# 1-Schematic_1d_Ping_Pong.net
KiCad netlist of a schematic drawn in EasyEDA
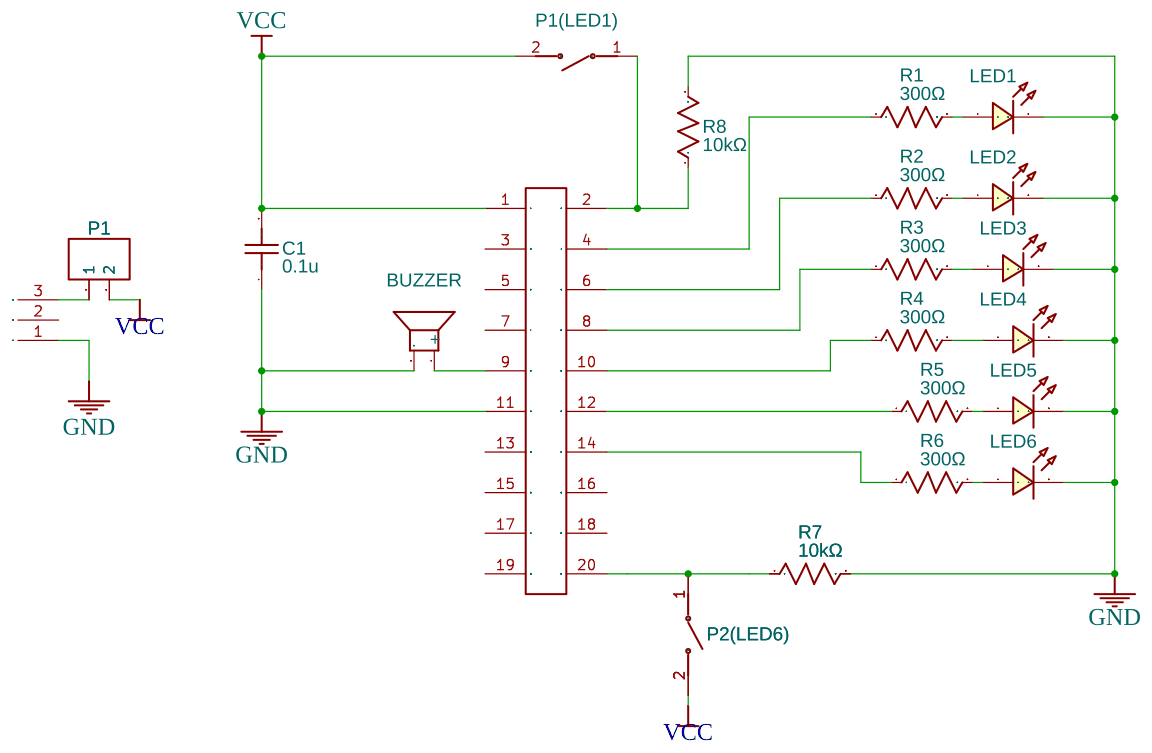
[diagram p0: schematic sheet]

(export (version "E")
  (design (tool "Eeschema 10.0.6"))
  (components
    (comp (ref "BUZZER")
      (value "BUZZER-12X9")
      (fields (field (name "Manufacturer Part") "buzzer-12X9"))
      (libsource (lib "") (part "BUZZER-12X9"))
    )
    (comp (ref "C1") (value "0.1u") (libsource (lib "") (part "C_0603_US")))
    (comp (ref "LED1")
      (value "LED-0603_R")
      (fields
        (field (name "Manufacturer Part") "19-217/R6C-AL1M2VY/3T")
        (field (name "Manufacturer") "EVERLIGHT(台湾亿光)")
      )
      (libsource (lib "") (part "LED-0603_R"))
    )
    (comp (ref "LED2")
      (value "LED-0603_R")
      (fields
        (field (name "Manufacturer Part") "19-217/R6C-AL1M2VY/3T")
        (field (name "Manufacturer") "EVERLIGHT(台湾亿光)")
      )
      (libsource (lib "") (part "LED-0603_R"))
    )
    (comp (ref "LED3")
      (value "LED-0603_R")
      (fields
        (field (name "Manufacturer Part") "19-217/R6C-AL1M2VY/3T")
        (field (name "Manufacturer") "EVERLIGHT(台湾亿光)")
      )
      (libsource (lib "") (part "LED-0603_R"))
    )
    (comp (ref "LED4")
      (value "LED-0603_R")
      (fields
        (field (name "Manufacturer Part") "19-217/R6C-AL1M2VY/3T")
        (field (name "Manufacturer") "EVERLIGHT(台湾亿光)")
      )
      (libsource (lib "") (part "LED-0603_R"))
    )
    (comp (ref "LED5")
      (value "LED-0603_R")
      (fields
        (field (name "Manufacturer Part") "19-217/R6C-AL1M2VY/3T")
        (field (name "Manufacturer") "EVERLIGHT(台湾亿光)")
      )
      (libsource (lib "") (part "LED-0603_R"))
    )
    (comp (ref "LED6")
      (value "LED-0603_R")
      (fields
        (field (name "Manufacturer Part") "19-217/R6C-AL1M2VY/3T")
        (field (name "Manufacturer") "EVERLIGHT(台湾亿光)")
      )
      (libsource (lib "") (part "LED-0603_R"))
    )
    (comp (ref "P1") (value "CONN-TH_2P-P5.00") (libsource (lib "") (part "CONN-TH_2P-P5.00")))
    (comp (ref "P1(LED1)") (value "BUTTON") (libsource (lib "") (part "BUTTON_1")))
    (comp (ref "P2(LED6)") (value "BUTTON") (libsource (lib "") (part "BUTTON")))
    (comp (ref "R1") (value "300Ω") (libsource (lib "") (part "R_0603_US")))
    (comp (ref "R2") (value "300Ω") (libsource (lib "") (part "R_0603_US")))
    (comp (ref "R3") (value "300Ω") (libsource (lib "") (part "R_0603_US")))
    (comp (ref "R4") (value "300Ω") (libsource (lib "") (part "R_0603_US")))
    (comp (ref "R5") (value "300Ω") (libsource (lib "") (part "R_0603_US")))
    (comp (ref "R6") (value "300Ω") (libsource (lib "") (part "R_0603_US")))
    (comp (ref "R7") (value "10kΩ") (libsource (lib "") (part "R_0603_US")))
    (comp (ref "R8") (value "10kΩ") (libsource (lib "") (part "R_0603_US_1")))
    (comp (ref "U1") (value "Tumbler_Large") (libsource (lib "") (part "Tumbler_Large")))
    (comp (ref "X1") (value "PIN_HEADER_2x10") (libsource (lib "") (part "PIN_HEADER_2x10")))
  )
  (nets
    (net (code "1") (name "GND") (class "Default")
      (node (ref "BUZZER") (pin "2") (pinfunction "2_2") (pintype "unspecified"))
      (node (ref "C1") (pin "1") (pinfunction "1_1") (pintype "unspecified"))
      (node (ref "LED1") (pin "2") (pinfunction "2_2") (pintype "unspecified"))
      (node (ref "LED2") (pin "2") (pinfunction "2_2") (pintype "unspecified"))
      (node (ref "LED3") (pin "2") (pinfunction "2_2") (pintype "unspecified"))
      (node (ref "LED4") (pin "2") (pinfunction "2_2") (pintype "unspecified"))
      (node (ref "LED5") (pin "2") (pinfunction "2_2") (pintype "unspecified"))
      (node (ref "LED6") (pin "2") (pinfunction "2_2") (pintype "unspecified"))
      (node (ref "R7") (pin "2") (pinfunction "2_2") (pintype "unspecified"))
      (node (ref "R8") (pin "2") (pinfunction "2_2") (pintype "unspecified"))
      (node (ref "U1") (pin "1") (pinfunction "1_1") (pintype "unspecified"))
      (node (ref "X1") (pin "11") (pinfunction "11_11") (pintype "unspecified"))
    )
    (net (code "2") (name "Net-(BUZZER-+)") (class "Default")
      (node (ref "BUZZER") (pin "1") (pinfunction "+_1") (pintype "unspecified"))
      (node (ref "X1") (pin "9") (pinfunction "9_9") (pintype "unspecified"))
    )
    (net (code "3") (name "Net-(LED1-Pad1)") (class "Default")
      (node (ref "LED1") (pin "1") (pinfunction "1_1") (pintype "unspecified"))
      (node (ref "R1") (pin "2") (pinfunction "2_2") (pintype "unspecified"))
    )
    (net (code "4") (name "Net-(LED2-Pad1)") (class "Default")
      (node (ref "LED2") (pin "1") (pinfunction "1_1") (pintype "unspecified"))
      (node (ref "R2") (pin "2") (pinfunction "2_2") (pintype "unspecified"))
    )
    (net (code "5") (name "Net-(LED3-Pad1)") (class "Default")
      (node (ref "LED3") (pin "1") (pinfunction "1_1") (pintype "unspecified"))
      (node (ref "R3") (pin "2") (pinfunction "2_2") (pintype "unspecified"))
    )
    (net (code "6") (name "Net-(LED4-Pad1)") (class "Default")
      (node (ref "LED4") (pin "1") (pinfunction "1_1") (pintype "unspecified"))
      (node (ref "R4") (pin "2") (pinfunction "2_2") (pintype "unspecified"))
    )
    (net (code "7") (name "Net-(LED5-Pad1)") (class "Default")
      (node (ref "LED5") (pin "1") (pinfunction "1_1") (pintype "unspecified"))
      (node (ref "R5") (pin "2") (pinfunction "2_2") (pintype "unspecified"))
    )
    (net (code "8") (name "Net-(LED6-Pad1)") (class "Default")
      (node (ref "LED6") (pin "1") (pinfunction "1_1") (pintype "unspecified"))
      (node (ref "R6") (pin "2") (pinfunction "2_2") (pintype "unspecified"))
    )
    (net (code "9") (name "Net-(P1(LED1)-Pad1)") (class "Default")
      (node (ref "P1(LED1)") (pin "1") (pinfunction "1_1") (pintype "unspecified"))
      (node (ref "R8") (pin "1") (pinfunction "1_1") (pintype "unspecified"))
      (node (ref "X1") (pin "2") (pinfunction "2_2") (pintype "unspecified"))
    )
    (net (code "10") (name "Net-(P1-Pad1)") (class "Default")
      (node (ref "P1") (pin "1") (pinfunction "1_1") (pintype "unspecified"))
      (node (ref "U1") (pin "3") (pinfunction "3_3") (pintype "unspecified"))
    )
    (net (code "11") (name "Net-(P2(LED6)-Pad1)") (class "Default")
      (node (ref "P2(LED6)") (pin "1") (pinfunction "1_1") (pintype "unspecified"))
      (node (ref "R7") (pin "1") (pinfunction "1_1") (pintype "unspecified"))
      (node (ref "X1") (pin "20") (pinfunction "20_20") (pintype "unspecified"))
    )
    (net (code "12") (name "Net-(R1-Pad1)") (class "Default")
      (node (ref "R1") (pin "1") (pinfunction "1_1") (pintype "unspecified"))
      (node (ref "X1") (pin "4") (pinfunction "4_4") (pintype "unspecified"))
    )
    (net (code "13") (name "Net-(R2-Pad1)") (class "Default")
      (node (ref "R2") (pin "1") (pinfunction "1_1") (pintype "unspecified"))
      (node (ref "X1") (pin "6") (pinfunction "6_6") (pintype "unspecified"))
    )
    (net (code "14") (name "Net-(R3-Pad1)") (class "Default")
      (node (ref "R3") (pin "1") (pinfunction "1_1") (pintype "unspecified"))
      (node (ref "X1") (pin "8") (pinfunction "8_8") (pintype "unspecified"))
    )
    (net (code "15") (name "Net-(R4-Pad1)") (class "Default")
      (node (ref "R4") (pin "1") (pinfunction "1_1") (pintype "unspecified"))
      (node (ref "X1") (pin "10") (pinfunction "10_10") (pintype "unspecified"))
    )
    (net (code "16") (name "Net-(R5-Pad1)") (class "Default")
      (node (ref "R5") (pin "1") (pinfunction "1_1") (pintype "unspecified"))
      (node (ref "X1") (pin "12") (pinfunction "12_12") (pintype "unspecified"))
    )
    (net (code "17") (name "Net-(R6-Pad1)") (class "Default")
      (node (ref "R6") (pin "1") (pinfunction "1_1") (pintype "unspecified"))
      (node (ref "X1") (pin "14") (pinfunction "14_14") (pintype "unspecified"))
    )
    (net (code "18") (name "VCC") (class "Default")
      (node (ref "C1") (pin "2") (pinfunction "2_2") (pintype "unspecified"))
      (node (ref "P1") (pin "2") (pinfunction "2_2") (pintype "unspecified"))
      (node (ref "P1(LED1)") (pin "2") (pinfunction "2_2") (pintype "unspecified"))
      (node (ref "P2(LED6)") (pin "2") (pinfunction "2_2") (pintype "unspecified"))
      (node (ref "X1") (pin "1") (pinfunction "1_1") (pintype "unspecified"))
    )
    (net (code "19") (name "unconnected-(U1-Pad2)") (class "Default")
      (node (ref "U1") (pin "2") (pinfunction "2_2") (pintype "unspecified"))
    )
    (net (code "20") (name "unconnected-(X1-Pad3)") (class "Default")
      (node (ref "X1") (pin "3") (pinfunction "3_3") (pintype "unspecified"))
    )
    (net (code "21") (name "unconnected-(X1-Pad5)") (class "Default")
      (node (ref "X1") (pin "5") (pinfunction "5_5") (pintype "unspecified"))
    )
    (net (code "22") (name "unconnected-(X1-Pad7)") (class "Default")
      (node (ref "X1") (pin "7") (pinfunction "7_7") (pintype "unspecified"))
    )
    (net (code "23") (name "unconnected-(X1-Pad13)") (class "Default")
      (node (ref "X1") (pin "13") (pinfunction "13_13") (pintype "unspecified"))
    )
    (net (code "24") (name "unconnected-(X1-Pad15)") (class "Default")
      (node (ref "X1") (pin "15") (pinfunction "15_15") (pintype "unspecified"))
    )
    (net (code "25") (name "unconnected-(X1-Pad16)") (class "Default")
      (node (ref "X1") (pin "16") (pinfunction "16_16") (pintype "unspecified"))
    )
    (net (code "26") (name "unconnected-(X1-Pad17)") (class "Default")
      (node (ref "X1") (pin "17") (pinfunction "17_17") (pintype "unspecified"))
    )
    (net (code "27") (name "unconnected-(X1-Pad18)") (class "Default")
      (node (ref "X1") (pin "18") (pinfunction "18_18") (pintype "unspecified"))
    )
    (net (code "28") (name "unconnected-(X1-Pad19)") (class "Default")
      (node (ref "X1") (pin "19") (pinfunction "19_19") (pintype "unspecified"))
    )
  )
)
